# simple-bug-2n918-2.net
KiCad netlist of a schematic drawn in EAGLE
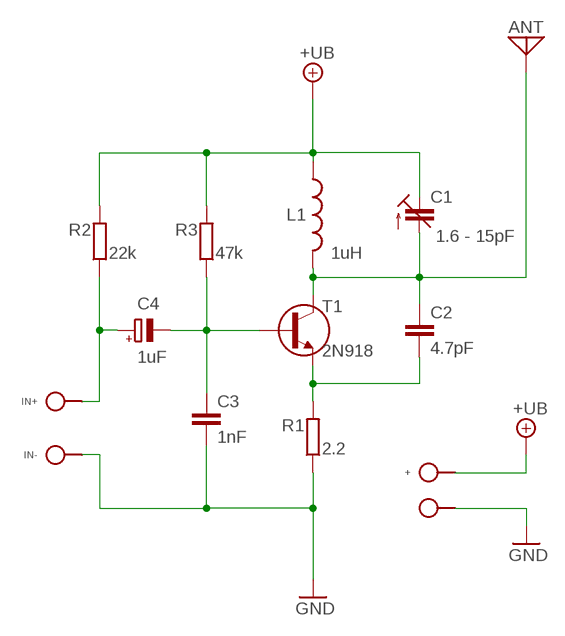
[diagram p0: schematic, sheet 1]

(export (version "E")
  (design (tool "Eeschema 10.0.6"))
  (components
    (comp (ref "+")
      (value "SPAD")
      (footprint "eagle-import:SPAD")
      (libsource (lib "eagle-import") (part "SPAD"))
    )
    (comp (ref "ANT")
      (value "ANT")
      (footprint "eagle-import:SPAD")
      (libsource (lib "eagle-import") (part "ANT"))
    )
    (comp (ref "C1")
      (value "1.6 - 15pF")
      (footprint "eagle-import:TRIM-2222-808")
      (libsource (lib "eagle-import") (part "C-TR-PH201272222-808-2PINB"))
    )
    (comp (ref "C2")
      (value "4.7pF")
      (footprint "eagle-import:C025-020X036")
      (libsource (lib "eagle-import") (part "C025-020X036"))
    )
    (comp (ref "C3")
      (value "1nF")
      (footprint "eagle-import:C025-020X036")
      (libsource (lib "eagle-import") (part "C025-020X036"))
    )
    (comp (ref "C4")
      (value "1uF")
      (footprint "eagle-import:E2,5-3")
      (libsource (lib "eagle-import") (part "CPOLE2,5-3"))
    )
    (comp (ref "IN+")
      (value "SPAD")
      (footprint "eagle-import:SPAD")
      (libsource (lib "eagle-import") (part "SPAD"))
    )
    (comp (ref "IN-")
      (value "SPAD")
      (footprint "eagle-import:SPAD")
      (libsource (lib "eagle-import") (part "SPAD"))
    )
    (comp (ref "L1")
      (value "1uH")
      (footprint "eagle-import:L-02_7")
      (libsource (lib "eagle-import") (part "L02/7"))
    )
    (comp (ref "R1")
      (value "2.2")
      (footprint "eagle-import:0202V")
      (libsource (lib "eagle-import") (part "R0202V"))
    )
    (comp (ref "R2")
      (value "22k")
      (footprint "eagle-import:0202_5")
      (libsource (lib "eagle-import") (part "R0202/5"))
    )
    (comp (ref "R3")
      (value "47k")
      (footprint "eagle-import:0202_5")
      (libsource (lib "eagle-import") (part "R0202/5"))
    )
    (comp (ref "T1")
      (value "2N918")
      (footprint "eagle-import:TO-72")
      (libsource (lib "eagle-import") (part "2N918TO-72"))
    )
    (comp (ref "̶̶")
      (value "SPAD")
      (footprint "eagle-import:SPAD")
      (libsource (lib "eagle-import") (part "SPAD"))
    )
  )
  (nets
    (net (code "1") (name "+UB") (class "Default")
      (node (ref "+") (pin "1") (pinfunction "P$1_1") (pintype "bidirectional"))
      (node (ref "C1") (pin "3") (pinfunction "A_3") (pintype "passive"))
      (node (ref "L1") (pin "1") (pinfunction "1_1") (pintype "passive"))
      (node (ref "R2") (pin "2") (pinfunction "2_2") (pintype "passive"))
      (node (ref "R3") (pin "2") (pinfunction "2_2") (pintype "passive"))
    )
    (net (code "2") (name "GND") (class "Default")
      (node (ref "C3") (pin "2") (pinfunction "2_2") (pintype "passive"))
      (node (ref "IN-") (pin "1") (pinfunction "P$1_1") (pintype "bidirectional"))
      (node (ref "R1") (pin "1") (pinfunction "1_1") (pintype "passive"))
      (node (ref "̶̶") (pin "1") (pinfunction "P$1_1") (pintype "bidirectional"))
    )
    (net (code "3") (name "Net-(C1-E)") (class "Default")
      (node (ref "ANT") (pin "1") (pinfunction "1_1") (pintype "output"))
      (node (ref "C1") (pin "2") (pinfunction "E_2") (pintype "passive"))
      (node (ref "C2") (pin "1") (pinfunction "1_1") (pintype "passive"))
      (node (ref "L1") (pin "2") (pinfunction "2_2") (pintype "passive"))
      (node (ref "T1") (pin "3") (pinfunction "C_3") (pintype "passive"))
    )
    (net (code "4") (name "Net-(IN+-P$1)") (class "Default")
      (node (ref "C4") (pin "+") (pinfunction "+_+") (pintype "passive"))
      (node (ref "IN+") (pin "1") (pinfunction "P$1_1") (pintype "bidirectional"))
      (node (ref "R2") (pin "1") (pinfunction "1_1") (pintype "passive"))
    )
    (net (code "5") (name "Net-(T1-B)") (class "Default")
      (node (ref "C3") (pin "1") (pinfunction "1_1") (pintype "passive"))
      (node (ref "C4") (pin "-") (pinfunction "-_-") (pintype "passive"))
      (node (ref "R3") (pin "1") (pinfunction "1_1") (pintype "passive"))
      (node (ref "T1") (pin "2") (pinfunction "B_2") (pintype "passive"))
    )
    (net (code "6") (name "Net-(T1-E)") (class "Default")
      (node (ref "C2") (pin "2") (pinfunction "2_2") (pintype "passive"))
      (node (ref "R1") (pin "2") (pinfunction "2_2") (pintype "passive"))
      (node (ref "T1") (pin "1") (pinfunction "E_1") (pintype "passive"))
    )
  )
)
